# Cassette_Interface_Manchester_lm358_lm39.net
KiCad netlist of a schematic drawn in EAGLE
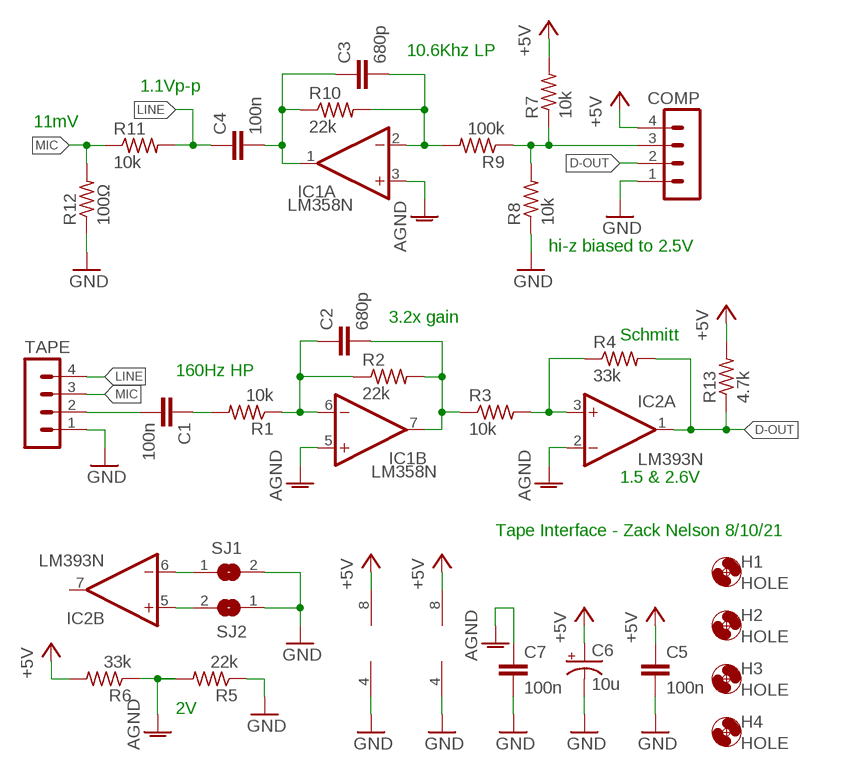
[diagram p0: schematic, sheet 1]

(export (version "E")
  (design (tool "Eeschema 10.0.6"))
  (components
    (comp (ref "C1")
      (value "100n")
      (footprint "eagle-import:C025-024X044")
      (libsource (lib "eagle-import") (part "C-EU025-024X044"))
    )
    (comp (ref "C2")
      (value "680p")
      (footprint "eagle-import:C025-024X044")
      (libsource (lib "eagle-import") (part "C-EU025-024X044"))
    )
    (comp (ref "C3")
      (value "680p")
      (footprint "eagle-import:C025-024X044")
      (libsource (lib "eagle-import") (part "C-EU025-024X044"))
    )
    (comp (ref "C4")
      (value "100n")
      (footprint "eagle-import:C025-024X044")
      (libsource (lib "eagle-import") (part "C-EU025-024X044"))
    )
    (comp (ref "C5")
      (value "100n")
      (footprint "eagle-import:C025-024X044")
      (libsource (lib "eagle-import") (part "C-EU025-024X044"))
    )
    (comp (ref "C6")
      (value "10u")
      (footprint "eagle-import:E2,5-5")
      (libsource (lib "eagle-import") (part "CPOL-USE2.5-5"))
    )
    (comp (ref "C7")
      (value "100n")
      (footprint "eagle-import:C025-024X044")
      (libsource (lib "eagle-import") (part "C-EU025-024X044"))
    )
    (comp (ref "COMP")
      (value "MA04-1")
      (footprint "eagle-import:MA04-1")
      (libsource (lib "eagle-import") (part "MA04-1"))
    )
    (comp (ref "H1")
      (value "HOLE")
      (footprint "eagle-import:3,0")
      (libsource (lib "eagle-import") (part "MOUNT-HOLE3.0"))
    )
    (comp (ref "H2")
      (value "HOLE")
      (footprint "eagle-import:3,0")
      (libsource (lib "eagle-import") (part "MOUNT-HOLE3.0"))
    )
    (comp (ref "H3")
      (value "HOLE")
      (footprint "eagle-import:3,0")
      (libsource (lib "eagle-import") (part "MOUNT-HOLE3.0"))
    )
    (comp (ref "H4")
      (value "HOLE")
      (footprint "eagle-import:3,0")
      (libsource (lib "eagle-import") (part "MOUNT-HOLE3.0"))
    )
    (comp (ref "IC1")
      (value "LM358N")
      (footprint "eagle-import:DIL08")
      (libsource (lib "eagle-import") (part "LM358N"))
    )
    (comp (ref "IC2")
      (value "LM393N")
      (footprint "eagle-import:DIL08")
      (libsource (lib "eagle-import") (part "LM393N"))
    )
    (comp (ref "R1")
      (value "10k")
      (footprint "eagle-import:0204V")
      (libsource (lib "eagle-import") (part "R-US_0204/2V"))
    )
    (comp (ref "R2")
      (value "22k")
      (footprint "eagle-import:0204V")
      (libsource (lib "eagle-import") (part "R-US_0204/2V"))
    )
    (comp (ref "R3")
      (value "10k")
      (footprint "eagle-import:0204V")
      (libsource (lib "eagle-import") (part "R-US_0204/2V"))
    )
    (comp (ref "R4")
      (value "33k")
      (footprint "eagle-import:0204V")
      (libsource (lib "eagle-import") (part "R-US_0204/2V"))
    )
    (comp (ref "R5")
      (value "22k")
      (footprint "eagle-import:0204V")
      (libsource (lib "eagle-import") (part "R-US_0204/2V"))
    )
    (comp (ref "R6")
      (value "33k")
      (footprint "eagle-import:0204V")
      (libsource (lib "eagle-import") (part "R-US_0204/2V"))
    )
    (comp (ref "R7")
      (value "10k")
      (footprint "eagle-import:0204V")
      (libsource (lib "eagle-import") (part "R-US_0204/2V"))
    )
    (comp (ref "R8")
      (value "10k")
      (footprint "eagle-import:0204V")
      (libsource (lib "eagle-import") (part "R-US_0204/2V"))
    )
    (comp (ref "R9")
      (value "100k")
      (footprint "eagle-import:0204V")
      (libsource (lib "eagle-import") (part "R-US_0204/2V"))
    )
    (comp (ref "R10")
      (value "22k")
      (footprint "eagle-import:0204V")
      (libsource (lib "eagle-import") (part "R-US_0204/2V"))
    )
    (comp (ref "R11")
      (value "10k")
      (footprint "eagle-import:0204V")
      (libsource (lib "eagle-import") (part "R-US_0204/2V"))
    )
    (comp (ref "R12")
      (value "100Ω")
      (footprint "eagle-import:0204V")
      (libsource (lib "eagle-import") (part "R-US_0204/2V"))
    )
    (comp (ref "R13")
      (value "4.7k")
      (footprint "eagle-import:0204V")
      (libsource (lib "eagle-import") (part "R-US_0204/2V"))
    )
    (comp (ref "SJ1") (value "SJ") (footprint "eagle-import:SJ") (libsource (lib "eagle-import") (part "SJ")))
    (comp (ref "SJ2") (value "SJ") (footprint "eagle-import:SJ") (libsource (lib "eagle-import") (part "SJ")))
    (comp (ref "TAPE")
      (value "MA04-1")
      (footprint "eagle-import:MA04-1")
      (libsource (lib "eagle-import") (part "MA04-1"))
    )
  )
  (nets
    (net (code "1") (name "+5V") (class "Default")
      (node (ref "C5") (pin "1") (pinfunction "1_1") (pintype "passive"))
      (node (ref "C6") (pin "+") (pinfunction "+_+") (pintype "passive"))
      (node (ref "COMP") (pin "4") (pinfunction "4_4") (pintype "passive"))
      (node (ref "IC1") (pin "8") (pinfunction "V+_8") (pintype "power_in"))
      (node (ref "IC2") (pin "8") (pinfunction "V+_8") (pintype "power_in"))
      (node (ref "R13") (pin "2") (pinfunction "2_2") (pintype "passive"))
      (node (ref "R6") (pin "2") (pinfunction "2_2") (pintype "passive"))
      (node (ref "R7") (pin "2") (pinfunction "2_2") (pintype "passive"))
    )
    (net (code "2") (name "AGND") (class "Default")
      (node (ref "C7") (pin "1") (pinfunction "1_1") (pintype "passive"))
      (node (ref "IC1") (pin "3") (pinfunction "+IN_3") (pintype "input"))
      (node (ref "IC1") (pin "5") (pinfunction "+IN_5") (pintype "input"))
      (node (ref "IC2") (pin "2") (pinfunction "-IN_2") (pintype "input"))
      (node (ref "R5") (pin "2") (pinfunction "2_2") (pintype "passive"))
      (node (ref "R6") (pin "1") (pinfunction "1_1") (pintype "passive"))
    )
    (net (code "3") (name "D-OUT") (class "Default")
      (node (ref "COMP") (pin "2") (pinfunction "2_2") (pintype "passive"))
      (node (ref "IC2") (pin "1") (pinfunction "OUT_1") (pintype "output"))
      (node (ref "R13") (pin "1") (pinfunction "1_1") (pintype "passive"))
      (node (ref "R4") (pin "2") (pinfunction "2_2") (pintype "passive"))
    )
    (net (code "4") (name "GND") (class "Default")
      (node (ref "C5") (pin "2") (pinfunction "2_2") (pintype "passive"))
      (node (ref "C6") (pin "-") (pinfunction "-_-") (pintype "passive"))
      (node (ref "C7") (pin "2") (pinfunction "2_2") (pintype "passive"))
      (node (ref "COMP") (pin "1") (pinfunction "1_1") (pintype "passive"))
      (node (ref "IC1") (pin "4") (pinfunction "V-_4") (pintype "power_in"))
      (node (ref "IC2") (pin "4") (pinfunction "V-_4") (pintype "power_in"))
      (node (ref "R12") (pin "1") (pinfunction "1_1") (pintype "passive"))
      (node (ref "R5") (pin "1") (pinfunction "1_1") (pintype "passive"))
      (node (ref "R8") (pin "1") (pinfunction "1_1") (pintype "passive"))
      (node (ref "SJ1") (pin "2") (pinfunction "2_2") (pintype "passive"))
      (node (ref "SJ2") (pin "1") (pinfunction "1_1") (pintype "passive"))
      (node (ref "TAPE") (pin "1") (pinfunction "1_1") (pintype "passive"))
    )
    (net (code "5") (name "LINE") (class "Default")
      (node (ref "C4") (pin "1") (pinfunction "1_1") (pintype "passive"))
      (node (ref "R11") (pin "2") (pinfunction "2_2") (pintype "passive"))
      (node (ref "TAPE") (pin "4") (pinfunction "4_4") (pintype "passive"))
    )
    (net (code "6") (name "MIC") (class "Default")
      (node (ref "R11") (pin "1") (pinfunction "1_1") (pintype "passive"))
      (node (ref "R12") (pin "2") (pinfunction "2_2") (pintype "passive"))
      (node (ref "TAPE") (pin "3") (pinfunction "3_3") (pintype "passive"))
    )
    (net (code "7") (name "Net-(C1-Pad1)") (class "Default")
      (node (ref "C1") (pin "1") (pinfunction "1_1") (pintype "passive"))
      (node (ref "R1") (pin "2") (pinfunction "2_2") (pintype "passive"))
    )
    (net (code "8") (name "Net-(C1-Pad2)") (class "Default")
      (node (ref "C1") (pin "2") (pinfunction "2_2") (pintype "passive"))
      (node (ref "TAPE") (pin "2") (pinfunction "2_2") (pintype "passive"))
    )
    (net (code "9") (name "Net-(COMP-Pad3)") (class "Default")
      (node (ref "COMP") (pin "3") (pinfunction "3_3") (pintype "passive"))
      (node (ref "R7") (pin "1") (pinfunction "1_1") (pintype "passive"))
      (node (ref "R8") (pin "2") (pinfunction "2_2") (pintype "passive"))
      (node (ref "R9") (pin "1") (pinfunction "1_1") (pintype "passive"))
    )
    (net (code "10") (name "Net-(IC1A--IN)") (class "Default")
      (node (ref "C3") (pin "2") (pinfunction "2_2") (pintype "passive"))
      (node (ref "IC1") (pin "2") (pinfunction "-IN_2") (pintype "input"))
      (node (ref "R10") (pin "2") (pinfunction "2_2") (pintype "passive"))
      (node (ref "R9") (pin "2") (pinfunction "2_2") (pintype "passive"))
    )
    (net (code "11") (name "Net-(IC1A-OUT)") (class "Default")
      (node (ref "C3") (pin "1") (pinfunction "1_1") (pintype "passive"))
      (node (ref "C4") (pin "2") (pinfunction "2_2") (pintype "passive"))
      (node (ref "IC1") (pin "1") (pinfunction "OUT_1") (pintype "output"))
      (node (ref "R10") (pin "1") (pinfunction "1_1") (pintype "passive"))
    )
    (net (code "12") (name "Net-(IC1B--IN)") (class "Default")
      (node (ref "C2") (pin "1") (pinfunction "1_1") (pintype "passive"))
      (node (ref "IC1") (pin "6") (pinfunction "-IN_6") (pintype "input"))
      (node (ref "R1") (pin "1") (pinfunction "1_1") (pintype "passive"))
      (node (ref "R2") (pin "1") (pinfunction "1_1") (pintype "passive"))
    )
    (net (code "13") (name "Net-(IC1B-OUT)") (class "Default")
      (node (ref "C2") (pin "2") (pinfunction "2_2") (pintype "passive"))
      (node (ref "IC1") (pin "7") (pinfunction "OUT_7") (pintype "output"))
      (node (ref "R2") (pin "2") (pinfunction "2_2") (pintype "passive"))
      (node (ref "R3") (pin "1") (pinfunction "1_1") (pintype "passive"))
    )
    (net (code "14") (name "Net-(IC2A-+IN)") (class "Default")
      (node (ref "IC2") (pin "3") (pinfunction "+IN_3") (pintype "input"))
      (node (ref "R3") (pin "2") (pinfunction "2_2") (pintype "passive"))
      (node (ref "R4") (pin "1") (pinfunction "1_1") (pintype "passive"))
    )
    (net (code "15") (name "Net-(IC2B-+IN)") (class "Default")
      (node (ref "IC2") (pin "5") (pinfunction "+IN_5") (pintype "input"))
      (node (ref "SJ2") (pin "2") (pinfunction "2_2") (pintype "passive"))
    )
    (net (code "16") (name "Net-(IC2B--IN)") (class "Default")
      (node (ref "IC2") (pin "6") (pinfunction "-IN_6") (pintype "input"))
      (node (ref "SJ1") (pin "1") (pinfunction "1_1") (pintype "passive"))
    )
    (net (code "17") (name "unconnected-(IC2B-OUT-Pad7)") (class "Default")
      (node (ref "IC2") (pin "7") (pinfunction "OUT_7") (pintype "output"))
    )
  )
)
